# Fortuna-v21-OtherMill-DoubleSided.net
KiCad netlist of a schematic drawn in EAGLE
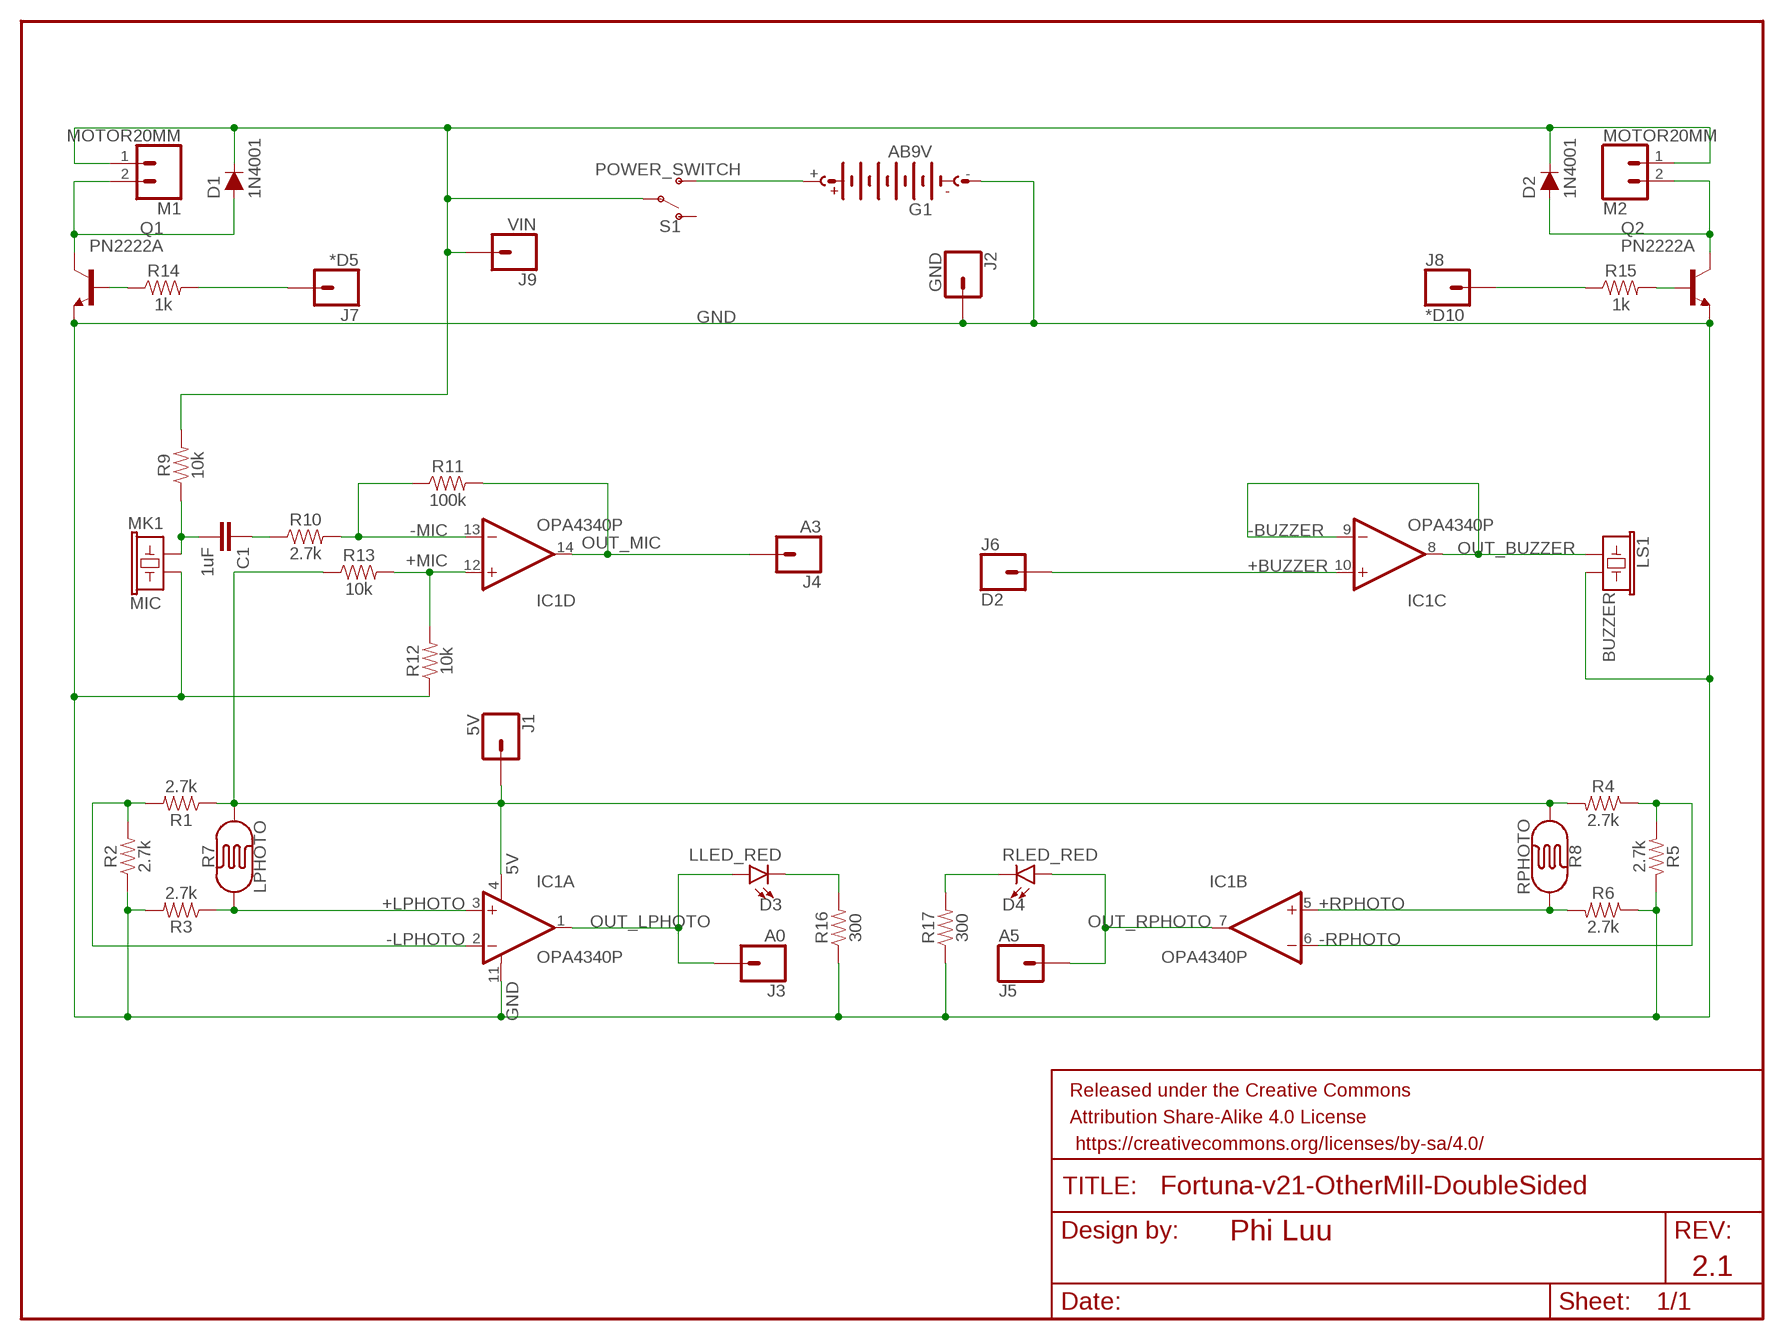
[diagram p0: schematic, sheet 1]

(export (version "E")
  (design (tool "Eeschema 10.0.6"))
  (components
    (comp (ref "C1")
      (value "1uF")
      (footprint "eagle-import:CAP-PTH-SMALL-KIT")
      (libsource (lib "eagle-import") (part "0.1UF-KIT-EZ-50V-20%"))
    )
    (comp (ref "D1")
      (value "1N4001")
      (footprint "eagle-import:DIODE-1N4148")
      (libsource (lib "eagle-import") (part "DIODE-1N4148"))
    )
    (comp (ref "D2")
      (value "1N4001")
      (footprint "eagle-import:DIODE-1N4148")
      (libsource (lib "eagle-import") (part "DIODE-1N4148"))
    )
    (comp (ref "D3")
      (value "LLED_RED")
      (footprint "eagle-import:LED_5MM")
      (libsource (lib "eagle-import") (part "LED5MM"))
    )
    (comp (ref "D4")
      (value "RLED_RED")
      (footprint "eagle-import:LED_5MM")
      (libsource (lib "eagle-import") (part "LED5MM"))
    )
    (comp (ref "FRAME1")
      (value "FRAME-LETTER")
      (footprint "eagle-import:CREATIVE_COMMONS")
      (libsource (lib "eagle-import") (part "FRAME-LETTER"))
    )
    (comp (ref "G1")
      (value "AB9V")
      (footprint "eagle-import:AB9V")
      (libsource (lib "eagle-import") (part "AB9V"))
    )
    (comp (ref "IC1")
      (value "OPA4340P")
      (footprint "eagle-import:DIL14")
      (libsource (lib "eagle-import") (part "OPA4340P"))
    )
    (comp (ref "J1")
      (value "5V")
      (footprint "eagle-import:1X01")
      (libsource (lib "eagle-import") (part "CONN_01"))
    )
    (comp (ref "J2")
      (value "GND")
      (footprint "eagle-import:1X01")
      (libsource (lib "eagle-import") (part "CONN_01"))
    )
    (comp (ref "J3")
      (value "A0")
      (footprint "eagle-import:1X01")
      (libsource (lib "eagle-import") (part "CONN_01"))
    )
    (comp (ref "J4")
      (value "A3")
      (footprint "eagle-import:1X01")
      (libsource (lib "eagle-import") (part "CONN_01"))
    )
    (comp (ref "J5")
      (value "A5")
      (footprint "eagle-import:1X01")
      (libsource (lib "eagle-import") (part "CONN_01"))
    )
    (comp (ref "J6")
      (value "D2")
      (footprint "eagle-import:1X01")
      (libsource (lib "eagle-import") (part "CONN_01"))
    )
    (comp (ref "J7")
      (value "*D5")
      (footprint "eagle-import:1X01")
      (libsource (lib "eagle-import") (part "CONN_01"))
    )
    (comp (ref "J8")
      (value "*D10")
      (footprint "eagle-import:1X01")
      (libsource (lib "eagle-import") (part "CONN_01"))
    )
    (comp (ref "J9")
      (value "VIN")
      (footprint "eagle-import:1X01")
      (libsource (lib "eagle-import") (part "CONN_01"))
    )
    (comp (ref "LS1")
      (value "BUZZER")
      (footprint "eagle-import:BUZZER-12MM")
      (libsource (lib "eagle-import") (part "BUZZER-PTH"))
    )
    (comp (ref "M1")
      (value "MOTOR20MM")
      (footprint "eagle-import:1X02")
      (libsource (lib "eagle-import") (part "CONN_02"))
    )
    (comp (ref "M2")
      (value "MOTOR20MM")
      (footprint "eagle-import:1X02")
      (libsource (lib "eagle-import") (part "CONN_02"))
    )
    (comp (ref "MK1")
      (value "MIC")
      (footprint "eagle-import:MICROPHONE-PTH-9.7MM")
      (libsource (lib "eagle-import") (part "MIC-PTH"))
    )
    (comp (ref "Q1")
      (value "PN2222A")
      (footprint "eagle-import:TO92-EBC-OVAL")
      (libsource (lib "eagle-import") (part "2N2222"))
    )
    (comp (ref "Q2")
      (value "PN2222A")
      (footprint "eagle-import:TO92-EBC-OVAL")
      (libsource (lib "eagle-import") (part "2N2222"))
    )
    (comp (ref "R1")
      (value "2.7k")
      (footprint "eagle-import:AXIAL-0.3")
      (libsource (lib "eagle-import") (part "1KOHM-HORIZ-1/4W-5%"))
    )
    (comp (ref "R2")
      (value "2.7k")
      (footprint "eagle-import:AXIAL-0.3")
      (libsource (lib "eagle-import") (part "1KOHM-HORIZ-1/4W-5%"))
    )
    (comp (ref "R3")
      (value "2.7k")
      (footprint "eagle-import:AXIAL-0.3")
      (libsource (lib "eagle-import") (part "1KOHM-HORIZ-1/4W-5%"))
    )
    (comp (ref "R4")
      (value "2.7k")
      (footprint "eagle-import:AXIAL-0.3")
      (libsource (lib "eagle-import") (part "1KOHM-HORIZ-1/4W-5%"))
    )
    (comp (ref "R5")
      (value "2.7k")
      (footprint "eagle-import:AXIAL-0.3")
      (libsource (lib "eagle-import") (part "1KOHM-HORIZ-1/4W-5%"))
    )
    (comp (ref "R6")
      (value "2.7k")
      (footprint "eagle-import:AXIAL-0.3")
      (libsource (lib "eagle-import") (part "1KOHM-HORIZ-1/4W-5%"))
    )
    (comp (ref "R7")
      (value "LPHOTO")
      (footprint "eagle-import:PHOTOCELL")
      (libsource (lib "eagle-import") (part "PHOTOCELLPTH"))
    )
    (comp (ref "R8")
      (value "RPHOTO")
      (footprint "eagle-import:PHOTOCELL")
      (libsource (lib "eagle-import") (part "PHOTOCELLPTH"))
    )
    (comp (ref "R9")
      (value "10k")
      (footprint "eagle-import:AXIAL-0.3")
      (libsource (lib "eagle-import") (part "1KOHM-HORIZ-1/4W-5%"))
    )
    (comp (ref "R10")
      (value "2.7k")
      (footprint "eagle-import:AXIAL-0.3")
      (libsource (lib "eagle-import") (part "1KOHM-HORIZ-1/4W-5%"))
    )
    (comp (ref "R11")
      (value "100k")
      (footprint "eagle-import:AXIAL-0.3")
      (libsource (lib "eagle-import") (part "1KOHM-HORIZ-1/4W-5%"))
    )
    (comp (ref "R12")
      (value "10k")
      (footprint "eagle-import:AXIAL-0.3")
      (libsource (lib "eagle-import") (part "1KOHM-HORIZ-1/4W-5%"))
    )
    (comp (ref "R13")
      (value "10k")
      (footprint "eagle-import:AXIAL-0.3")
      (libsource (lib "eagle-import") (part "1KOHM-HORIZ-1/4W-5%"))
    )
    (comp (ref "R14")
      (value "1k")
      (footprint "eagle-import:AXIAL-0.3")
      (libsource (lib "eagle-import") (part "1KOHM-HORIZ-1/4W-5%"))
    )
    (comp (ref "R15")
      (value "1k")
      (footprint "eagle-import:AXIAL-0.3")
      (libsource (lib "eagle-import") (part "1KOHM-HORIZ-1/4W-5%"))
    )
    (comp (ref "R16")
      (value "300")
      (footprint "eagle-import:AXIAL-0.3")
      (libsource (lib "eagle-import") (part "1KOHM-HORIZ-1/4W-5%"))
    )
    (comp (ref "R17")
      (value "300")
      (footprint "eagle-import:AXIAL-0.3")
      (libsource (lib "eagle-import") (part "1KOHM-HORIZ-1/4W-5%"))
    )
    (comp (ref "S1")
      (value "POWER_SWITCH")
      (footprint "eagle-import:SWITCH_SPDT_PTH_11.6X4.0MM")
      (libsource (lib "eagle-import") (part "SWITCH-SPDT-PTH-11.6X4.0MM"))
    )
  )
  (nets
    (net (code "1") (name "/+LPHOTO") (class "Default")
      (node (ref "IC1") (pin "3") (pinfunction "+IN_3") (pintype "input"))
      (node (ref "R3") (pin "P$1") (pinfunction "1_P$1") (pintype "passive"))
      (node (ref "R7") (pin "1") (pinfunction "P$1_1") (pintype "bidirectional"))
    )
    (net (code "2") (name "/+MIC") (class "Default")
      (node (ref "IC1") (pin "12") (pinfunction "+IN_12") (pintype "input"))
      (node (ref "R12") (pin "P$2") (pinfunction "2_P$2") (pintype "passive"))
      (node (ref "R13") (pin "P$2") (pinfunction "2_P$2") (pintype "passive"))
    )
    (net (code "3") (name "/+RPHOTO") (class "Default")
      (node (ref "IC1") (pin "5") (pinfunction "+IN_5") (pintype "input"))
      (node (ref "R6") (pin "P$2") (pinfunction "2_P$2") (pintype "passive"))
      (node (ref "R8") (pin "1") (pinfunction "P$1_1") (pintype "bidirectional"))
    )
    (net (code "4") (name "/-LPHOTO") (class "Default")
      (node (ref "IC1") (pin "2") (pinfunction "-IN_2") (pintype "input"))
      (node (ref "R1") (pin "P$2") (pinfunction "2_P$2") (pintype "passive"))
      (node (ref "R2") (pin "P$2") (pinfunction "2_P$2") (pintype "passive"))
    )
    (net (code "5") (name "/-MIC") (class "Default")
      (node (ref "IC1") (pin "13") (pinfunction "-IN_13") (pintype "input"))
      (node (ref "R10") (pin "P$2") (pinfunction "2_P$2") (pintype "passive"))
      (node (ref "R11") (pin "P$1") (pinfunction "1_P$1") (pintype "passive"))
    )
    (net (code "6") (name "/-RPHOTO") (class "Default")
      (node (ref "IC1") (pin "6") (pinfunction "-IN_6") (pintype "input"))
      (node (ref "R4") (pin "P$1") (pinfunction "1_P$1") (pintype "passive"))
      (node (ref "R5") (pin "P$2") (pinfunction "2_P$2") (pintype "passive"))
    )
    (net (code "7") (name "/5V") (class "Default")
      (node (ref "IC1") (pin "4") (pinfunction "V+_4") (pintype "power_in"))
      (node (ref "J1") (pin "1") (pinfunction "1_1") (pintype "passive"))
      (node (ref "R1") (pin "P$1") (pinfunction "1_P$1") (pintype "passive"))
      (node (ref "R13") (pin "P$1") (pinfunction "1_P$1") (pintype "passive"))
      (node (ref "R4") (pin "P$2") (pinfunction "2_P$2") (pintype "passive"))
      (node (ref "R7") (pin "2") (pinfunction "P$2_2") (pintype "bidirectional"))
      (node (ref "R8") (pin "2") (pinfunction "P$2_2") (pintype "bidirectional"))
    )
    (net (code "8") (name "/GND") (class "Default")
      (node (ref "G1") (pin "-") (pinfunction "-_-") (pintype "passive"))
      (node (ref "IC1") (pin "11") (pinfunction "V-_11") (pintype "power_in"))
      (node (ref "J2") (pin "1") (pinfunction "1_1") (pintype "passive"))
      (node (ref "LS1") (pin "-") (pinfunction "2_-") (pintype "passive"))
      (node (ref "MK1") (pin "GND") (pinfunction "2_GND") (pintype "passive"))
      (node (ref "Q1") (pin "E") (pinfunction "E_E") (pintype "passive"))
      (node (ref "Q2") (pin "E") (pinfunction "E_E") (pintype "passive"))
      (node (ref "R12") (pin "P$1") (pinfunction "1_P$1") (pintype "passive"))
      (node (ref "R16") (pin "P$1") (pinfunction "1_P$1") (pintype "passive"))
      (node (ref "R17") (pin "P$1") (pinfunction "1_P$1") (pintype "passive"))
      (node (ref "R2") (pin "P$1") (pinfunction "1_P$1") (pintype "passive"))
      (node (ref "R3") (pin "P$2") (pinfunction "2_P$2") (pintype "passive"))
      (node (ref "R5") (pin "P$1") (pinfunction "1_P$1") (pintype "passive"))
      (node (ref "R6") (pin "P$1") (pinfunction "1_P$1") (pintype "passive"))
    )
    (net (code "9") (name "/OUT_BUZZER") (class "Default")
      (node (ref "IC1") (pin "8") (pinfunction "OUT_8") (pintype "output"))
      (node (ref "IC1") (pin "9") (pinfunction "-IN_9") (pintype "input"))
      (node (ref "LS1") (pin "+") (pinfunction "1_+") (pintype "passive"))
    )
    (net (code "10") (name "/OUT_LPHOTO") (class "Default")
      (node (ref "D3") (pin "A") (pinfunction "A_A") (pintype "passive"))
      (node (ref "IC1") (pin "1") (pinfunction "OUT_1") (pintype "output"))
      (node (ref "J3") (pin "1") (pinfunction "1_1") (pintype "passive"))
    )
    (net (code "11") (name "/OUT_MIC") (class "Default")
      (node (ref "IC1") (pin "14") (pinfunction "OUT_14") (pintype "output"))
      (node (ref "J4") (pin "1") (pinfunction "1_1") (pintype "passive"))
      (node (ref "R11") (pin "P$2") (pinfunction "2_P$2") (pintype "passive"))
    )
    (net (code "12") (name "/OUT_RPHOTO") (class "Default")
      (node (ref "D4") (pin "A") (pinfunction "A_A") (pintype "passive"))
      (node (ref "IC1") (pin "7") (pinfunction "OUT_7") (pintype "output"))
      (node (ref "J5") (pin "1") (pinfunction "1_1") (pintype "passive"))
    )
    (net (code "13") (name "Net-(D1-PadA)") (class "Default")
      (node (ref "D1") (pin "A") (pinfunction "A_A") (pintype "passive"))
      (node (ref "M1") (pin "2") (pinfunction "2_2") (pintype "passive"))
      (node (ref "Q1") (pin "C") (pinfunction "C_C") (pintype "passive"))
    )
    (net (code "14") (name "Net-(D2-PadA)") (class "Default")
      (node (ref "D2") (pin "A") (pinfunction "A_A") (pintype "passive"))
      (node (ref "M2") (pin "2") (pinfunction "2_2") (pintype "passive"))
      (node (ref "Q2") (pin "C") (pinfunction "C_C") (pintype "passive"))
    )
    (net (code "15") (name "Net-(D3-C)") (class "Default")
      (node (ref "D3") (pin "K") (pinfunction "C_K") (pintype "passive"))
      (node (ref "R16") (pin "P$2") (pinfunction "2_P$2") (pintype "passive"))
    )
    (net (code "16") (name "Net-(D4-C)") (class "Default")
      (node (ref "D4") (pin "K") (pinfunction "C_K") (pintype "passive"))
      (node (ref "R17") (pin "P$2") (pinfunction "2_P$2") (pintype "passive"))
    )
    (net (code "17") (name "Net-(IC1C-+IN)") (class "Default")
      (node (ref "IC1") (pin "10") (pinfunction "+IN_10") (pintype "input"))
      (node (ref "J6") (pin "1") (pinfunction "1_1") (pintype "passive"))
    )
    (net (code "18") (name "Net-(MK1-1)") (class "Default")
      (node (ref "C1") (pin "2") (pinfunction "2_2") (pintype "passive"))
      (node (ref "MK1") (pin "OUT") (pinfunction "1_OUT") (pintype "passive"))
      (node (ref "R9") (pin "P$1") (pinfunction "1_P$1") (pintype "passive"))
    )
    (net (code "19") (name "Net-(R9-2)") (class "Default")
      (node (ref "D1") (pin "C") (pinfunction "C_C") (pintype "passive"))
      (node (ref "D2") (pin "C") (pinfunction "C_C") (pintype "passive"))
      (node (ref "J9") (pin "1") (pinfunction "1_1") (pintype "passive"))
      (node (ref "M1") (pin "1") (pinfunction "1_1") (pintype "passive"))
      (node (ref "M2") (pin "1") (pinfunction "1_1") (pintype "passive"))
      (node (ref "R9") (pin "P$2") (pinfunction "2_P$2") (pintype "passive"))
      (node (ref "S1") (pin "2") (pinfunction "P_2") (pintype "passive"))
    )
    (net (code "20") (name "Net-(R10-1)") (class "Default")
      (node (ref "C1") (pin "1") (pinfunction "1_1") (pintype "passive"))
      (node (ref "R10") (pin "P$1") (pinfunction "1_P$1") (pintype "passive"))
    )
    (net (code "21") (name "Net-(R14-1)") (class "Default")
      (node (ref "Q1") (pin "B") (pinfunction "B_B") (pintype "passive"))
      (node (ref "R14") (pin "P$1") (pinfunction "1_P$1") (pintype "passive"))
    )
    (net (code "22") (name "Net-(R14-2)") (class "Default")
      (node (ref "J7") (pin "1") (pinfunction "1_1") (pintype "passive"))
      (node (ref "R14") (pin "P$2") (pinfunction "2_P$2") (pintype "passive"))
    )
    (net (code "23") (name "Net-(R15-1)") (class "Default")
      (node (ref "J8") (pin "1") (pinfunction "1_1") (pintype "passive"))
      (node (ref "R15") (pin "P$1") (pinfunction "1_P$1") (pintype "passive"))
    )
    (net (code "24") (name "Net-(R15-2)") (class "Default")
      (node (ref "Q2") (pin "B") (pinfunction "B_B") (pintype "passive"))
      (node (ref "R15") (pin "P$2") (pinfunction "2_P$2") (pintype "passive"))
    )
    (net (code "25") (name "Net-(S1-S)") (class "Default")
      (node (ref "G1") (pin "+") (pinfunction "+_+") (pintype "passive"))
      (node (ref "S1") (pin "3") (pinfunction "S_3") (pintype "passive"))
    )
    (net (code "26") (name "unconnected-(S1-O-Pad1)") (class "Default")
      (node (ref "S1") (pin "1") (pinfunction "O_1") (pintype "passive"))
    )
  )
)
